# module_SIM800C.net
KiCad netlist of a schematic drawn in EAGLE
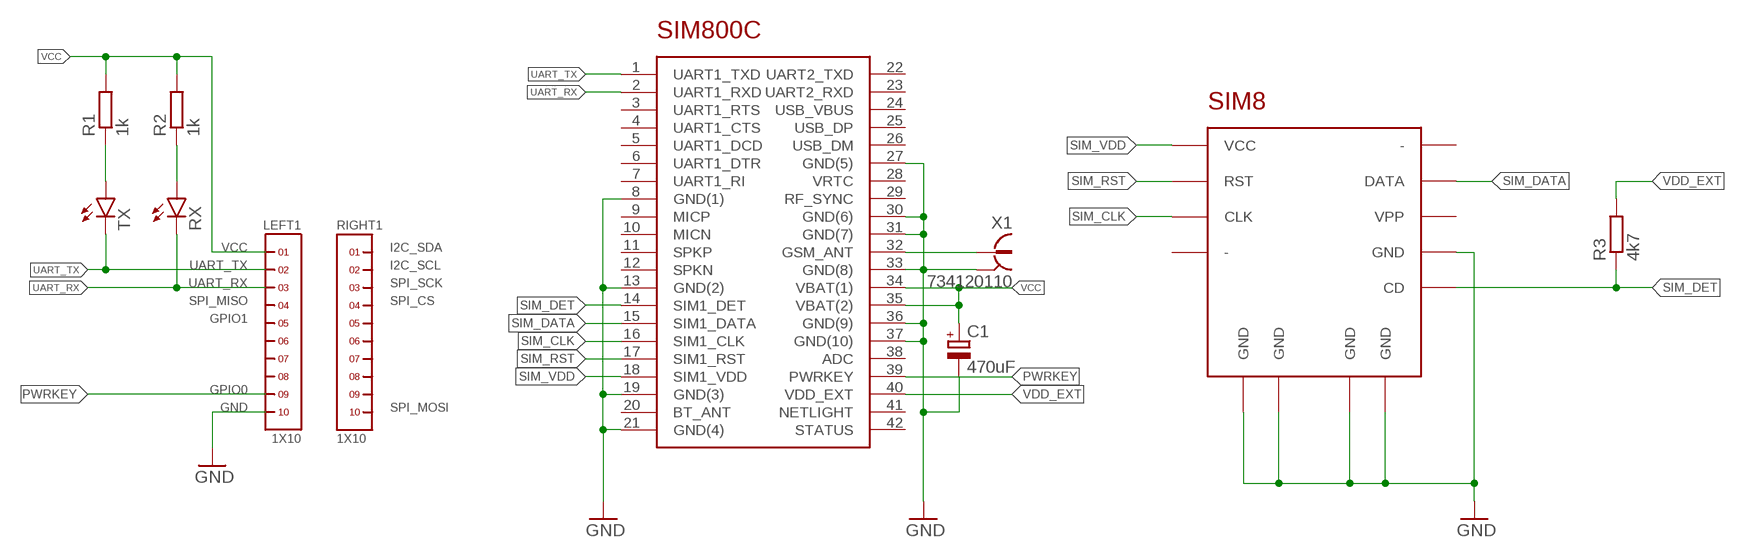
[diagram p0: schematic, sheet 1]

(export (version "E")
  (design (tool "Eeschema 10.0.6"))
  (components
    (comp (ref "C1")
      (value "470uF")
      (footprint "eagle-import:SMC_D")
      (libsource (lib "eagle-import") (part "CPOL-EUSMCD"))
    )
    (comp (ref "IC1")
      (value "SIM800C")
      (footprint "eagle-import:SIM800C")
      (libsource (lib "eagle-import") (part "SIM800C"))
    )
    (comp (ref "LEFT1")
      (value "1X10")
      (footprint "eagle-import:1X10")
      (libsource (lib "eagle-import") (part "1X10"))
    )
    (comp (ref "R1")
      (value "1k")
      (footprint "eagle-import:R0603")
      (libsource (lib "eagle-import") (part "R-EU_R0603"))
    )
    (comp (ref "R2")
      (value "1k")
      (footprint "eagle-import:R0603")
      (libsource (lib "eagle-import") (part "R-EU_R0603"))
    )
    (comp (ref "R3")
      (value "4k7")
      (footprint "eagle-import:R0603")
      (libsource (lib "eagle-import") (part "R-EU_R0603"))
    )
    (comp (ref "RIGHT1")
      (value "1X10")
      (footprint "eagle-import:1X10")
      (libsource (lib "eagle-import") (part "1X10"))
    )
    (comp (ref "RX")
      (value "LEDCHIPLED_0603")
      (footprint "eagle-import:CHIPLED_0603")
      (libsource (lib "eagle-import") (part "LEDCHIPLED_0603"))
    )
    (comp (ref "TX")
      (value "LEDCHIPLED_0603")
      (footprint "eagle-import:CHIPLED_0603")
      (libsource (lib "eagle-import") (part "LEDCHIPLED_0603"))
    )
    (comp (ref "U$2")
      (value "115Q-BCA0")
      (footprint "eagle-import:115Q-BCA0")
      (libsource (lib "eagle-import") (part "115Q-BCA0"))
    )
    (comp (ref "X1")
      (value "734120110")
      (footprint "eagle-import:734120110")
      (libsource (lib "eagle-import") (part "734120110"))
    )
  )
  (nets
    (net (code "1") (name "GND") (class "Default")
      (node (ref "C1") (pin "-") (pinfunction "-_-") (pintype "passive"))
      (node (ref "IC1") (pin "13") (pinfunction "GND(2)_13") (pintype "input"))
      (node (ref "IC1") (pin "19") (pinfunction "GND(3)_19") (pintype "input"))
      (node (ref "IC1") (pin "21") (pinfunction "GND(4)_21") (pintype "input"))
      (node (ref "IC1") (pin "27") (pinfunction "GND(5)_27") (pintype "input"))
      (node (ref "IC1") (pin "30") (pinfunction "GND(6)_30") (pintype "input"))
      (node (ref "IC1") (pin "31") (pinfunction "GND(7)_31") (pintype "input"))
      (node (ref "IC1") (pin "33") (pinfunction "GND(8)_33") (pintype "input"))
      (node (ref "IC1") (pin "36") (pinfunction "GND(9)_36") (pintype "input"))
      (node (ref "IC1") (pin "37") (pinfunction "GND(10)_37") (pintype "input"))
      (node (ref "IC1") (pin "8") (pinfunction "GND(1)_8") (pintype "input"))
      (node (ref "LEFT1") (pin "10") (pinfunction "10_10") (pintype "bidirectional"))
      (node (ref "U$2") (pin "P$10") (pinfunction "GND_P$10") (pintype "bidirectional"))
      (node (ref "U$2") (pin "P$11") (pinfunction "GND_P$11") (pintype "bidirectional"))
      (node (ref "U$2") (pin "P$12") (pinfunction "GND_P$12") (pintype "bidirectional"))
      (node (ref "U$2") (pin "P$13") (pinfunction "GND_P$13") (pintype "bidirectional"))
      (node (ref "U$2") (pin "P$5") (pinfunction "GND_P$5") (pintype "bidirectional"))
      (node (ref "X1") (pin "S@1") (pinfunction "2_S@1") (pintype "passive"))
      (node (ref "X1") (pin "S@2") (pinfunction "2_S@2") (pintype "passive"))
      (node (ref "X1") (pin "S@3") (pinfunction "2_S@3") (pintype "passive"))
    )
    (net (code "2") (name "Net-(IC1-GSM_ANT)") (class "Default")
      (node (ref "IC1") (pin "32") (pinfunction "GSM_ANT_32") (pintype "input"))
      (node (ref "X1") (pin "1") (pinfunction "1_1") (pintype "passive"))
    )
    (net (code "3") (name "Net-(R1-Pad1)") (class "Default")
      (node (ref "R1") (pin "1") (pinfunction "1_1") (pintype "passive"))
      (node (ref "TX") (pin "A") (pinfunction "A_A") (pintype "passive"))
    )
    (net (code "4") (name "Net-(R2-Pad1)") (class "Default")
      (node (ref "R2") (pin "1") (pinfunction "1_1") (pintype "passive"))
      (node (ref "RX") (pin "A") (pinfunction "A_A") (pintype "passive"))
    )
    (net (code "5") (name "PWRKEY") (class "Default")
      (node (ref "IC1") (pin "39") (pinfunction "PWRKEY_39") (pintype "input"))
      (node (ref "LEFT1") (pin "9") (pinfunction "9_9") (pintype "bidirectional"))
    )
    (net (code "6") (name "SIM_CLK") (class "Default")
      (node (ref "IC1") (pin "16") (pinfunction "SIM1_CLK_16") (pintype "input"))
      (node (ref "U$2") (pin "P$3") (pinfunction "CLK_P$3") (pintype "bidirectional"))
    )
    (net (code "7") (name "SIM_DATA") (class "Default")
      (node (ref "IC1") (pin "15") (pinfunction "SIM1_DATA_15") (pintype "input"))
      (node (ref "U$2") (pin "P$7") (pinfunction "DATA_P$7") (pintype "bidirectional"))
    )
    (net (code "8") (name "SIM_DET") (class "Default")
      (node (ref "IC1") (pin "14") (pinfunction "SIM1_DET_14") (pintype "input"))
      (node (ref "R3") (pin "1") (pinfunction "1_1") (pintype "passive"))
      (node (ref "U$2") (pin "P$9") (pinfunction "CD_P$9") (pintype "bidirectional"))
    )
    (net (code "9") (name "SIM_RST") (class "Default")
      (node (ref "IC1") (pin "17") (pinfunction "SIM1_RST_17") (pintype "input"))
      (node (ref "U$2") (pin "P$2") (pinfunction "RST_P$2") (pintype "bidirectional"))
    )
    (net (code "10") (name "SIM_VDD") (class "Default")
      (node (ref "IC1") (pin "18") (pinfunction "SIM1_VDD_18") (pintype "input"))
      (node (ref "U$2") (pin "P$1") (pinfunction "VCC_P$1") (pintype "bidirectional"))
    )
    (net (code "11") (name "UART_RX") (class "Default")
      (node (ref "IC1") (pin "2") (pinfunction "UART1_RXD_2") (pintype "input"))
      (node (ref "LEFT1") (pin "3") (pinfunction "3_3") (pintype "bidirectional"))
      (node (ref "RX") (pin "C") (pinfunction "C_C") (pintype "passive"))
    )
    (net (code "12") (name "UART_TX") (class "Default")
      (node (ref "IC1") (pin "1") (pinfunction "UART1_TXD_1") (pintype "input"))
      (node (ref "LEFT1") (pin "2") (pinfunction "2_2") (pintype "bidirectional"))
      (node (ref "TX") (pin "C") (pinfunction "C_C") (pintype "passive"))
    )
    (net (code "13") (name "VCC") (class "Default")
      (node (ref "C1") (pin "+") (pinfunction "+_+") (pintype "passive"))
      (node (ref "IC1") (pin "34") (pinfunction "VBAT(1)_34") (pintype "input"))
      (node (ref "IC1") (pin "35") (pinfunction "VBAT(2)_35") (pintype "input"))
      (node (ref "LEFT1") (pin "1") (pinfunction "1_1") (pintype "bidirectional"))
      (node (ref "R1") (pin "2") (pinfunction "2_2") (pintype "passive"))
      (node (ref "R2") (pin "2") (pinfunction "2_2") (pintype "passive"))
    )
    (net (code "14") (name "VDD_EXT") (class "Default")
      (node (ref "IC1") (pin "40") (pinfunction "VDD_EXT_40") (pintype "input"))
      (node (ref "R3") (pin "2") (pinfunction "2_2") (pintype "passive"))
    )
    (net (code "15") (name "unconnected-(IC1-ADC-Pad38)") (class "Default")
      (node (ref "IC1") (pin "38") (pinfunction "ADC_38") (pintype "input"))
    )
    (net (code "16") (name "unconnected-(IC1-BT_ANT-Pad20)") (class "Default")
      (node (ref "IC1") (pin "20") (pinfunction "BT_ANT_20") (pintype "input"))
    )
    (net (code "17") (name "unconnected-(IC1-MICN-Pad10)") (class "Default")
      (node (ref "IC1") (pin "10") (pinfunction "MICN_10") (pintype "input"))
    )
    (net (code "18") (name "unconnected-(IC1-MICP-Pad9)") (class "Default")
      (node (ref "IC1") (pin "9") (pinfunction "MICP_9") (pintype "input"))
    )
    (net (code "19") (name "unconnected-(IC1-NETLIGHT-Pad41)") (class "Default")
      (node (ref "IC1") (pin "41") (pinfunction "NETLIGHT_41") (pintype "input"))
    )
    (net (code "20") (name "unconnected-(IC1-RF_SYNC-Pad29)") (class "Default")
      (node (ref "IC1") (pin "29") (pinfunction "RF_SYNC_29") (pintype "input"))
    )
    (net (code "21") (name "unconnected-(IC1-SPKN-Pad12)") (class "Default")
      (node (ref "IC1") (pin "12") (pinfunction "SPKN_12") (pintype "input"))
    )
    (net (code "22") (name "unconnected-(IC1-SPKP-Pad11)") (class "Default")
      (node (ref "IC1") (pin "11") (pinfunction "SPKP_11") (pintype "input"))
    )
    (net (code "23") (name "unconnected-(IC1-STATUS-Pad42)") (class "Default")
      (node (ref "IC1") (pin "42") (pinfunction "STATUS_42") (pintype "input"))
    )
    (net (code "24") (name "unconnected-(IC1-UART1_CTS-Pad4)") (class "Default")
      (node (ref "IC1") (pin "4") (pinfunction "UART1_CTS_4") (pintype "input"))
    )
    (net (code "25") (name "unconnected-(IC1-UART1_DCD-Pad5)") (class "Default")
      (node (ref "IC1") (pin "5") (pinfunction "UART1_DCD_5") (pintype "input"))
    )
    (net (code "26") (name "unconnected-(IC1-UART1_DTR-Pad6)") (class "Default")
      (node (ref "IC1") (pin "6") (pinfunction "UART1_DTR_6") (pintype "input"))
    )
    (net (code "27") (name "unconnected-(IC1-UART1_RI-Pad7)") (class "Default")
      (node (ref "IC1") (pin "7") (pinfunction "UART1_RI_7") (pintype "input"))
    )
    (net (code "28") (name "unconnected-(IC1-UART1_RTS-Pad3)") (class "Default")
      (node (ref "IC1") (pin "3") (pinfunction "UART1_RTS_3") (pintype "input"))
    )
    (net (code "29") (name "unconnected-(IC1-UART2_RXD-Pad23)") (class "Default")
      (node (ref "IC1") (pin "23") (pinfunction "UART2_RXD_23") (pintype "input"))
    )
    (net (code "30") (name "unconnected-(IC1-UART2_TXD-Pad22)") (class "Default")
      (node (ref "IC1") (pin "22") (pinfunction "UART2_TXD_22") (pintype "input"))
    )
    (net (code "31") (name "unconnected-(IC1-USB_DM-Pad26)") (class "Default")
      (node (ref "IC1") (pin "26") (pinfunction "USB_DM_26") (pintype "input"))
    )
    (net (code "32") (name "unconnected-(IC1-USB_DP-Pad25)") (class "Default")
      (node (ref "IC1") (pin "25") (pinfunction "USB_DP_25") (pintype "input"))
    )
    (net (code "33") (name "unconnected-(IC1-USB_VBUS-Pad24)") (class "Default")
      (node (ref "IC1") (pin "24") (pinfunction "USB_VBUS_24") (pintype "input"))
    )
    (net (code "34") (name "unconnected-(IC1-VRTC-Pad28)") (class "Default")
      (node (ref "IC1") (pin "28") (pinfunction "VRTC_28") (pintype "input"))
    )
    (net (code "35") (name "unconnected-(LEFT1-Pad4)") (class "Default")
      (node (ref "LEFT1") (pin "4") (pinfunction "4_4") (pintype "bidirectional"))
    )
    (net (code "36") (name "unconnected-(LEFT1-Pad5)") (class "Default")
      (node (ref "LEFT1") (pin "5") (pinfunction "5_5") (pintype "bidirectional"))
    )
    (net (code "37") (name "unconnected-(LEFT1-Pad6)") (class "Default")
      (node (ref "LEFT1") (pin "6") (pinfunction "6_6") (pintype "bidirectional"))
    )
    (net (code "38") (name "unconnected-(LEFT1-Pad7)") (class "Default")
      (node (ref "LEFT1") (pin "7") (pinfunction "7_7") (pintype "bidirectional"))
    )
    (net (code "39") (name "unconnected-(LEFT1-Pad8)") (class "Default")
      (node (ref "LEFT1") (pin "8") (pinfunction "8_8") (pintype "bidirectional"))
    )
    (net (code "40") (name "unconnected-(RIGHT1-Pad1)") (class "Default")
      (node (ref "RIGHT1") (pin "1") (pinfunction "1_1") (pintype "bidirectional"))
    )
    (net (code "41") (name "unconnected-(RIGHT1-Pad2)") (class "Default")
      (node (ref "RIGHT1") (pin "2") (pinfunction "2_2") (pintype "bidirectional"))
    )
    (net (code "42") (name "unconnected-(RIGHT1-Pad3)") (class "Default")
      (node (ref "RIGHT1") (pin "3") (pinfunction "3_3") (pintype "bidirectional"))
    )
    (net (code "43") (name "unconnected-(RIGHT1-Pad4)") (class "Default")
      (node (ref "RIGHT1") (pin "4") (pinfunction "4_4") (pintype "bidirectional"))
    )
    (net (code "44") (name "unconnected-(RIGHT1-Pad5)") (class "Default")
      (node (ref "RIGHT1") (pin "5") (pinfunction "5_5") (pintype "bidirectional"))
    )
    (net (code "45") (name "unconnected-(RIGHT1-Pad6)") (class "Default")
      (node (ref "RIGHT1") (pin "6") (pinfunction "6_6") (pintype "bidirectional"))
    )
    (net (code "46") (name "unconnected-(RIGHT1-Pad7)") (class "Default")
      (node (ref "RIGHT1") (pin "7") (pinfunction "7_7") (pintype "bidirectional"))
    )
    (net (code "47") (name "unconnected-(RIGHT1-Pad8)") (class "Default")
      (node (ref "RIGHT1") (pin "8") (pinfunction "8_8") (pintype "bidirectional"))
    )
    (net (code "48") (name "unconnected-(RIGHT1-Pad9)") (class "Default")
      (node (ref "RIGHT1") (pin "9") (pinfunction "9_9") (pintype "bidirectional"))
    )
    (net (code "49") (name "unconnected-(RIGHT1-Pad10)") (class "Default")
      (node (ref "RIGHT1") (pin "10") (pinfunction "10_10") (pintype "bidirectional"))
    )
    (net (code "50") (name "unconnected-(U$2---PadP$4)") (class "Default")
      (node (ref "U$2") (pin "P$4") (pinfunction "-_P$4") (pintype "bidirectional"))
    )
    (net (code "51") (name "unconnected-(U$2---PadP$8)") (class "Default")
      (node (ref "U$2") (pin "P$8") (pinfunction "-_P$8") (pintype "bidirectional"))
    )
    (net (code "52") (name "unconnected-(U$2-VPP-PadP$6)") (class "Default")
      (node (ref "U$2") (pin "P$6") (pinfunction "VPP_P$6") (pintype "bidirectional"))
    )
  )
)
